# 02-ESP32.net
KiCad netlist of a schematic drawn in Altium Designer
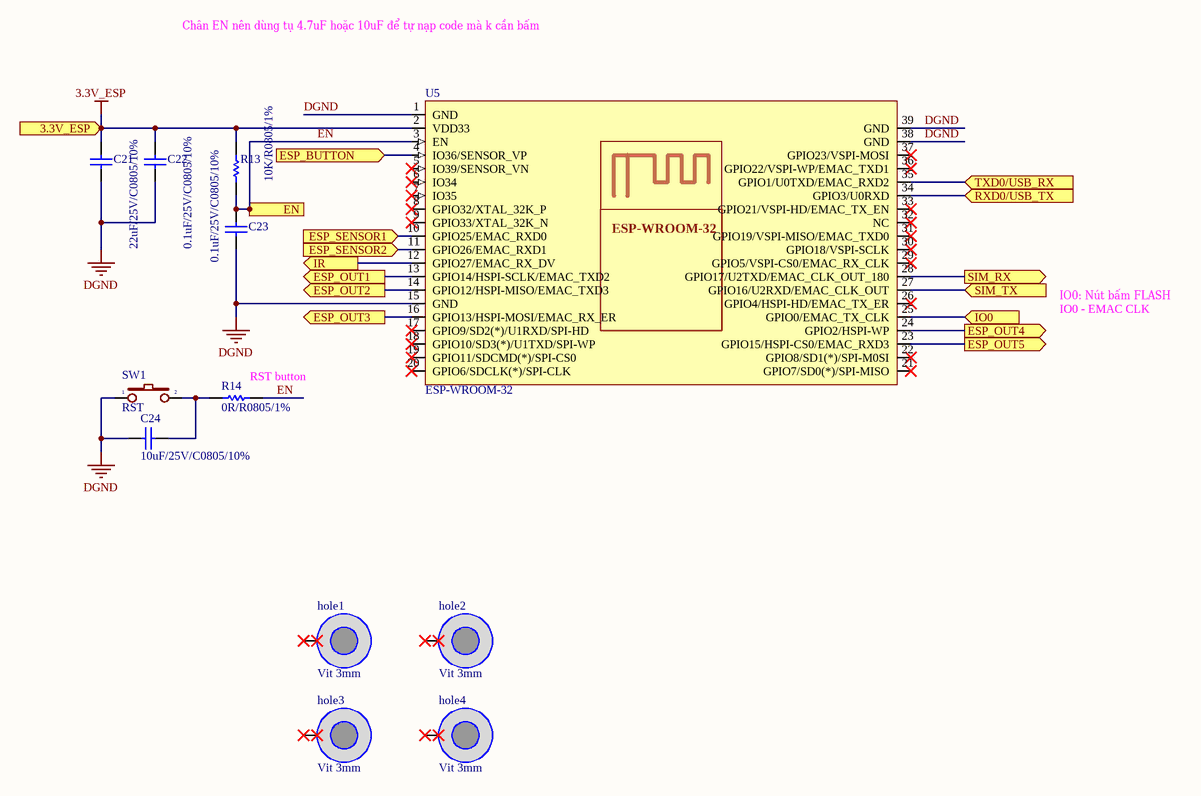
[diagram p0: 02-ESP32.SchDoc]

(export (version "E")
  (design (tool "Eeschema 10.0.6"))
  (components
    (comp (ref "C21")
      (value "22uF/25V/C0805/10%")
      (footprint "CAP_CERA_C2012(CC0805INCH)")
      (description "22µF ±20% 25V Ceramic Capacitor X5R 0805 (2012 Metric)")
      (fields (field (name "MANUFACTURER") "Tariff Applied"))
      (libsource (lib "GSHT_181013") (part "0.1uF/50V/C0603/10%"))
    )
    (comp (ref "C22")
      (value "0.1uF/25V/C0805/10%")
      (footprint "CAP_CERA_C2012(CC0805INCH)")
      (description "0.1µF ±10% 25V Ceramic Capacitor X7R 0805 (2012 Metric)")
      (libsource (lib "GSHT_181013") (part "0.1uF/50V/C0603/10%"))
    )
    (comp (ref "C23")
      (value "0.1uF/25V/C0805/10%")
      (footprint "CAP_CERA_C2012(CC0805INCH)")
      (description "0.1µF ±10% 25V Ceramic Capacitor X7R 0805 (2012 Metric)")
      (libsource (lib "GSHT_181013") (part "0.1uF/50V/C0603/10%"))
    )
    (comp (ref "C24")
      (value "10uF/25V/C0805/10%")
      (footprint "CAP_CERA_C2012(CC0805INCH)")
      (description "0.1µF ±10% 25V Ceramic Capacitor X7R 0805 (2012 Metric)")
      (libsource (lib "GSHT_181013") (part "0.1uF/50V/C0603/10%"))
    )
    (comp (ref "hole1") (value "Vit 3mm") (footprint "Screw 3.0") (libsource (lib "lpson") (part "Vit 3mm")))
    (comp (ref "hole2") (value "Vit 3mm") (footprint "Screw 3.0") (libsource (lib "lpson") (part "Vit 3mm")))
    (comp (ref "hole3") (value "Vit 3mm") (footprint "Screw 3.0") (libsource (lib "lpson") (part "Vit 3mm")))
    (comp (ref "hole4") (value "Vit 3mm") (footprint "Screw 3.0") (libsource (lib "lpson") (part "Vit 3mm")))
    (comp (ref "R13")
      (value "10K/R0805/1%")
      (footprint "Res 0805 SMD")
      (description "10 kOhms ±1% 0.125W, 1/8W Chip Resistor 0805 (2012 Metric) Thick Film")
      (libsource (lib "GSHT_181013") (part "200K/R0603/1%"))
    )
    (comp (ref "R14")
      (value "0R/R0805/1%")
      (footprint "Res 0805 SMD")
      (description "0 Ohms Jumper 0.125W, 1/8W Chip Resistor 0805 (2012 Metric) Automotive AEC-Q200 Thick Film")
      (libsource (lib "GSHT_181013") (part "200K/R0603/1%"))
    )
    (comp (ref "SW1")
      (value "RST")
      (footprint "Button 3x4mm")
      (description "SWITCH TACTILE SPST-NO 0.05A 12V")
      (libsource (lib "lpson") (part "SW2"))
    )
    (comp (ref "U5")
      (value "ESP-WROOM-32")
      (footprint "ESP32 WROOM")
      (description "ESP-WROOM-32 (8MB), WIFI MODULE 64 MBITS SPI FLASH")
      (libsource (lib "lpson") (part "ESP-WROOM-32"))
    )
  )
  (nets
    (net (code "1") (name "/EN") (class "Default")
      (node (ref "C23") (pin "2") (pinfunction "2_2") (pintype "passive"))
      (node (ref "R13") (pin "2") (pinfunction "2_2") (pintype "passive"))
      (node (ref "R14") (pin "2") (pinfunction "2_2") (pintype "passive"))
      (node (ref "U5") (pin "3") (pinfunction "EN_3") (pintype "input"))
    )
    (net (code "2") (name "/ESP_BUTTON") (class "Default")
      (node (ref "U5") (pin "4") (pinfunction "IO36/SENSOR_VP_4") (pintype "input"))
    )
    (net (code "3") (name "/ESP_OUT1") (class "Default")
      (node (ref "U5") (pin "13") (pinfunction "GPIO14/HSPI-SCLK/EMAC_TXD2_13") (pintype "passive"))
    )
    (net (code "4") (name "/ESP_OUT2") (class "Default")
      (node (ref "U5") (pin "14") (pinfunction "GPIO12/HSPI-MISO/EMAC_TXD3_14") (pintype "passive"))
    )
    (net (code "5") (name "/ESP_OUT3") (class "Default")
      (node (ref "U5") (pin "16") (pinfunction "GPIO13/HSPI-MOSI/EMAC_RX_ER_16") (pintype "passive"))
    )
    (net (code "6") (name "/ESP_OUT4") (class "Default")
      (node (ref "U5") (pin "24") (pinfunction "GPIO2/HSPI-WP_24") (pintype "passive"))
    )
    (net (code "7") (name "/ESP_OUT5") (class "Default")
      (node (ref "U5") (pin "23") (pinfunction "GPIO15/HSPI-CS0/EMAC_RXD3_23") (pintype "passive"))
    )
    (net (code "8") (name "/ESP_SENSOR1") (class "Default")
      (node (ref "U5") (pin "10") (pinfunction "GPIO25/EMAC_RXD0_10") (pintype "passive"))
    )
    (net (code "9") (name "/ESP_SENSOR2") (class "Default")
      (node (ref "U5") (pin "11") (pinfunction "GPIO26/EMAC_RXD1_11") (pintype "passive"))
    )
    (net (code "10") (name "/IO0") (class "Default")
      (node (ref "U5") (pin "25") (pinfunction "GPIO0/EMAC_TX_CLK_25") (pintype "passive"))
    )
    (net (code "11") (name "/IR") (class "Default")
      (node (ref "U5") (pin "12") (pinfunction "GPIO27/EMAC_RX_DV_12") (pintype "passive"))
    )
    (net (code "12") (name "/RXD0{slash}USB_TX") (class "Default")
      (node (ref "U5") (pin "34") (pinfunction "GPIO3/U0RXD_34") (pintype "passive"))
    )
    (net (code "13") (name "/SIM_RX") (class "Default")
      (node (ref "U5") (pin "28") (pinfunction "GPIO17/U2TXD/EMAC_CLK_OUT_180_28") (pintype "passive"))
    )
    (net (code "14") (name "/SIM_TX") (class "Default")
      (node (ref "U5") (pin "27") (pinfunction "GPIO16/U2RXD/EMAC_CLK_OUT_27") (pintype "passive"))
    )
    (net (code "15") (name "/TXD0{slash}USB_RX") (class "Default")
      (node (ref "U5") (pin "35") (pinfunction "GPIO1/U0TXD/EMAC_RXD2_35") (pintype "passive"))
    )
    (net (code "16") (name "3.3V_ESP") (class "Default")
      (node (ref "C21") (pin "2") (pinfunction "2_2") (pintype "passive"))
      (node (ref "C22") (pin "2") (pinfunction "2_2") (pintype "passive"))
      (node (ref "R13") (pin "1") (pinfunction "1_1") (pintype "passive"))
      (node (ref "U5") (pin "2") (pinfunction "VDD33_2") (pintype "passive"))
    )
    (net (code "17") (name "DGND") (class "Default")
      (node (ref "C21") (pin "1") (pinfunction "1_1") (pintype "passive"))
      (node (ref "C22") (pin "1") (pinfunction "1_1") (pintype "passive"))
      (node (ref "C23") (pin "1") (pinfunction "1_1") (pintype "passive"))
      (node (ref "C24") (pin "2") (pinfunction "2_2") (pintype "passive"))
      (node (ref "SW1") (pin "1") (pinfunction "1_1") (pintype "passive"))
      (node (ref "U5") (pin "1") (pinfunction "GND_1") (pintype "passive"))
      (node (ref "U5") (pin "15") (pinfunction "GND_15") (pintype "passive"))
      (node (ref "U5") (pin "38") (pinfunction "GND_38") (pintype "passive"))
      (node (ref "U5") (pin "39") (pinfunction "GND_39") (pintype "passive"))
    )
    (net (code "18") (name "Net-(C24-Pad1)") (class "Default")
      (node (ref "C24") (pin "1") (pinfunction "1_1") (pintype "passive"))
      (node (ref "R14") (pin "1") (pinfunction "1_1") (pintype "passive"))
      (node (ref "SW1") (pin "2") (pinfunction "2_2") (pintype "passive"))
    )
    (net (code "19") (name "unconnected-(U5-GPIO4{slash}HSPI-HD{slash}EMAC_TX_ER-Pad26)") (class "Default")
      (node (ref "U5") (pin "26") (pinfunction "GPIO4/HSPI-HD/EMAC_TX_ER_26") (pintype "passive+no_connect"))
    )
    (net (code "20") (name "unconnected-(U5-GPIO5{slash}VSPI-CS0{slash}EMAC_RX_CLK-Pad29)") (class "Default")
      (node (ref "U5") (pin "29") (pinfunction "GPIO5/VSPI-CS0/EMAC_RX_CLK_29") (pintype "passive+no_connect"))
    )
    (net (code "21") (name "unconnected-(U5-GPIO6{slash}SDCLK(*){slash}SPI-CLK-Pad20)") (class "Default")
      (node (ref "U5") (pin "20") (pinfunction "GPIO6/SDCLK(*)/SPI-CLK_20") (pintype "passive+no_connect"))
    )
    (net (code "22") (name "unconnected-(U5-GPIO7{slash}SD0(*){slash}SPI-MISO-Pad21)") (class "Default")
      (node (ref "U5") (pin "21") (pinfunction "GPIO7/SD0(*)/SPI-MISO_21") (pintype "passive+no_connect"))
    )
    (net (code "23") (name "unconnected-(U5-GPIO8{slash}SD1(*){slash}SPI-M0SI-Pad22)") (class "Default")
      (node (ref "U5") (pin "22") (pinfunction "GPIO8/SD1(*)/SPI-M0SI_22") (pintype "passive+no_connect"))
    )
    (net (code "24") (name "unconnected-(U5-GPIO9{slash}SD2(*){slash}U1RXD{slash}SPI-HD-Pad17)") (class "Default")
      (node (ref "U5") (pin "17") (pinfunction "GPIO9/SD2(*)/U1RXD/SPI-HD_17") (pintype "passive+no_connect"))
    )
    (net (code "25") (name "unconnected-(U5-GPIO10{slash}SD3(*){slash}U1TXD{slash}SPI-WP-Pad18)") (class "Default")
      (node (ref "U5") (pin "18") (pinfunction "GPIO10/SD3(*)/U1TXD/SPI-WP_18") (pintype "passive+no_connect"))
    )
    (net (code "26") (name "unconnected-(U5-GPIO11{slash}SDCMD(*){slash}SPI-CS0-Pad19)") (class "Default")
      (node (ref "U5") (pin "19") (pinfunction "GPIO11/SDCMD(*)/SPI-CS0_19") (pintype "passive+no_connect"))
    )
    (net (code "27") (name "unconnected-(U5-GPIO18{slash}VSPI-SCLK-Pad30)") (class "Default")
      (node (ref "U5") (pin "30") (pinfunction "GPIO18/VSPI-SCLK_30") (pintype "passive+no_connect"))
    )
    (net (code "28") (name "unconnected-(U5-GPIO19{slash}VSPI-MISO{slash}EMAC_TXD0-Pad31)") (class "Default")
      (node (ref "U5") (pin "31") (pinfunction "GPIO19/VSPI-MISO/EMAC_TXD0_31") (pintype "passive+no_connect"))
    )
    (net (code "29") (name "unconnected-(U5-GPIO21{slash}VSPI-HD{slash}EMAC_TX_EN-Pad33)") (class "Default")
      (node (ref "U5") (pin "33") (pinfunction "GPIO21/VSPI-HD/EMAC_TX_EN_33") (pintype "passive+no_connect"))
    )
    (net (code "30") (name "unconnected-(U5-GPIO22{slash}VSPI-WP{slash}EMAC_TXD1-Pad36)") (class "Default")
      (node (ref "U5") (pin "36") (pinfunction "GPIO22/VSPI-WP/EMAC_TXD1_36") (pintype "passive+no_connect"))
    )
    (net (code "31") (name "unconnected-(U5-GPIO23{slash}VSPI-MOSI-Pad37)") (class "Default")
      (node (ref "U5") (pin "37") (pinfunction "GPIO23/VSPI-MOSI_37") (pintype "passive+no_connect"))
    )
    (net (code "32") (name "unconnected-(U5-GPIO32{slash}XTAL_32K_P-Pad8)") (class "Default")
      (node (ref "U5") (pin "8") (pinfunction "GPIO32/XTAL_32K_P_8") (pintype "passive+no_connect"))
    )
    (net (code "33") (name "unconnected-(U5-GPIO33{slash}XTAL_32K_N-Pad9)") (class "Default")
      (node (ref "U5") (pin "9") (pinfunction "GPIO33/XTAL_32K_N_9") (pintype "passive+no_connect"))
    )
    (net (code "34") (name "unconnected-(U5-IO34-Pad6)") (class "Default")
      (node (ref "U5") (pin "6") (pinfunction "IO34_6") (pintype "input+no_connect"))
    )
    (net (code "35") (name "unconnected-(U5-IO35-Pad7)") (class "Default")
      (node (ref "U5") (pin "7") (pinfunction "IO35_7") (pintype "input+no_connect"))
    )
    (net (code "36") (name "unconnected-(U5-IO39{slash}SENSOR_VN-Pad5)") (class "Default")
      (node (ref "U5") (pin "5") (pinfunction "IO39/SENSOR_VN_5") (pintype "input+no_connect"))
    )
    (net (code "37") (name "unconnected-(U5-NC-Pad32)") (class "Default")
      (node (ref "U5") (pin "32") (pinfunction "NC_32") (pintype "passive+no_connect"))
    )
    (net (code "38") (name "unconnected-(hole1-hole-Pad1)") (class "Default")
      (node (ref "hole1") (pin "1") (pinfunction "hole_1") (pintype "passive+no_connect"))
    )
    (net (code "39") (name "unconnected-(hole2-hole-Pad1)") (class "Default")
      (node (ref "hole2") (pin "1") (pinfunction "hole_1") (pintype "passive+no_connect"))
    )
    (net (code "40") (name "unconnected-(hole3-hole-Pad1)") (class "Default")
      (node (ref "hole3") (pin "1") (pinfunction "hole_1") (pintype "passive+no_connect"))
    )
    (net (code "41") (name "unconnected-(hole4-hole-Pad1)") (class "Default")
      (node (ref "hole4") (pin "1") (pinfunction "hole_1") (pintype "passive+no_connect"))
    )
  )
)
